# IR-Controle-PC_EasyEDA.net
KiCad netlist of a schematic drawn in EasyEDA
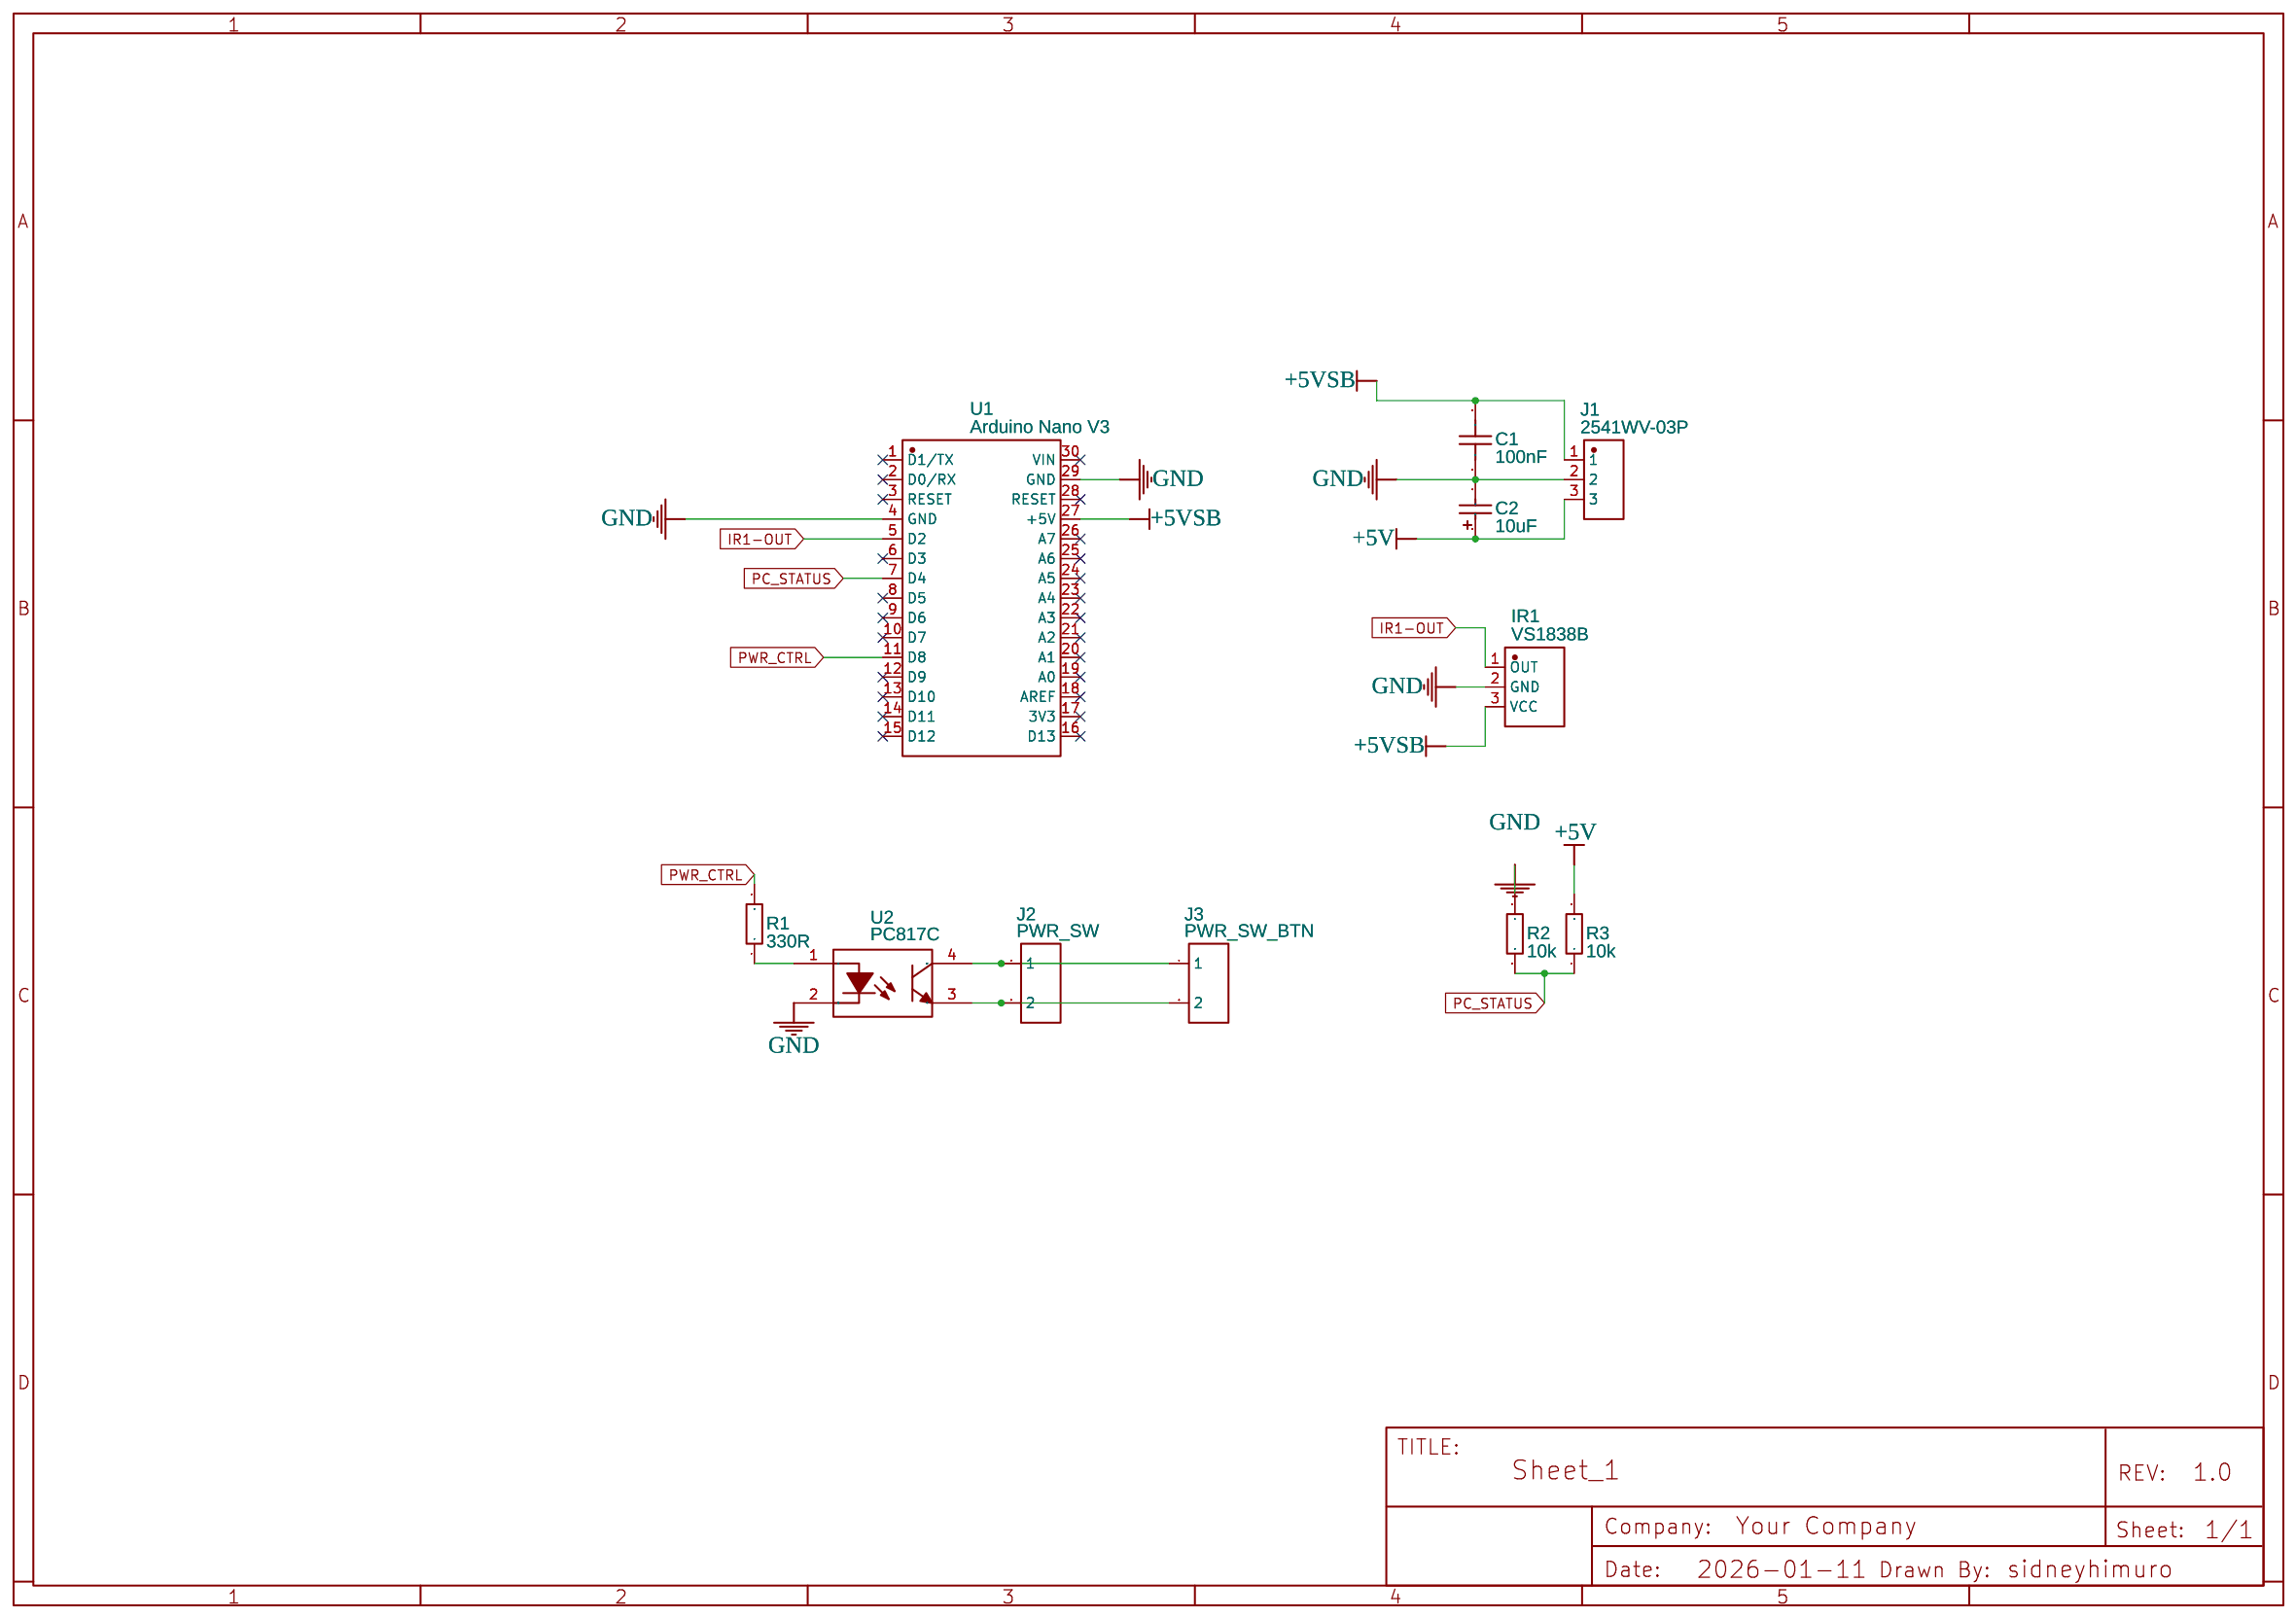
[diagram p0: schematic sheet]

(export (version "E")
  (design (tool "Eeschema 10.0.6"))
  (components
    (comp (ref "C1")
      (value "100nF")
      (fields (field (name "Manufacturer Part") "CT4-0805B103K500F3") (field (name "Manufacturer") "FH"))
      (libsource (lib "") (part "CT4-0805B103K500F3"))
    )
    (comp (ref "C2")
      (value "10uF")
      (fields (field (name "Manufacturer Part") "TAP106K035SCS") (field (name "Manufacturer") "AVX"))
      (libsource (lib "") (part "TAP106K035SCS"))
    )
    (comp (ref "IR1") (value "VS1838B") (libsource (lib "") (part "VS1838B")))
    (comp (ref "J1")
      (value "2541WV-03P")
      (fields (field (name "Manufacturer") "HanElectricity(瀚源)"))
      (libsource (lib "") (part "2541WV-03P"))
    )
    (comp (ref "J2")
      (value "PWR_SW")
      (fields
        (field (name "Manufacturer Part") "826629-2")
        (field (name "Manufacturer") "TE Connectivity(泰科电子)")
      )
      (libsource (lib "") (part "Header-Male-2.54_1x2"))
    )
    (comp (ref "J3")
      (value "PWR_SW_BTN")
      (fields
        (field (name "Manufacturer Part") "826629-2")
        (field (name "Manufacturer") "TE Connectivity(泰科电子)")
      )
      (libsource (lib "") (part "Header-Male-2.54_1x2"))
    )
    (comp (ref "R1")
      (value "330R")
      (fields (field (name "Manufacturer Part") "?"))
      (libsource (lib "") (part "Res_AXIAL-0.3(1/8W)_EU"))
    )
    (comp (ref "R2")
      (value "10k")
      (fields (field (name "Manufacturer Part") "?"))
      (libsource (lib "") (part "Res_AXIAL-0.3(1/8W)_EU_1"))
    )
    (comp (ref "R3")
      (value "10k")
      (fields (field (name "Manufacturer Part") "?"))
      (libsource (lib "") (part "Res_AXIAL-0.3(1/8W)_EU"))
    )
    (comp (ref "U1")
      (value "Arduino Nano V3")
      (fields (field (name "Manufacturer Part") "ARDUINO_NANO"))
      (libsource (lib "") (part "ARDUINO_NANO"))
    )
    (comp (ref "U2")
      (value "PC817C")
      (fields (field (name "Manufacturer") "华润华晶"))
      (libsource (lib "") (part "PC817C"))
    )
  )
  (nets
    (net (code "1") (name "+5V") (class "Default")
      (node (ref "C2") (pin "1") (pinfunction "1_1") (pintype "input"))
      (node (ref "J1") (pin "3") (pinfunction "3_3") (pintype "unspecified"))
      (node (ref "R3") (pin "2") (pinfunction "2_2") (pintype "unspecified"))
    )
    (net (code "2") (name "+5VSB") (class "Default")
      (node (ref "C1") (pin "2") (pinfunction "2_2") (pintype "unspecified"))
      (node (ref "IR1") (pin "3") (pinfunction "VCC_3") (pintype "unspecified"))
      (node (ref "J1") (pin "1") (pinfunction "1_1") (pintype "unspecified"))
      (node (ref "U1") (pin "27") (pinfunction "+5V_27") (pintype "unspecified"))
    )
    (net (code "3") (name "GND") (class "Default")
      (node (ref "C1") (pin "1") (pinfunction "1_1") (pintype "unspecified"))
      (node (ref "C2") (pin "2") (pinfunction "2_2") (pintype "input"))
      (node (ref "IR1") (pin "2") (pinfunction "GND_2") (pintype "unspecified"))
      (node (ref "J1") (pin "2") (pinfunction "2_2") (pintype "unspecified"))
      (node (ref "R2") (pin "1") (pinfunction "1_1") (pintype "unspecified"))
      (node (ref "U1") (pin "29") (pinfunction "GND_29") (pintype "unspecified"))
      (node (ref "U1") (pin "4") (pinfunction "GND_4") (pintype "unspecified"))
      (node (ref "U2") (pin "2") (pinfunction "CAT_2") (pintype "unspecified"))
    )
    (net (code "4") (name "IR1-OUT") (class "Default")
      (node (ref "IR1") (pin "1") (pinfunction "OUT_1") (pintype "unspecified"))
      (node (ref "U1") (pin "5") (pinfunction "D2_5") (pintype "unspecified"))
    )
    (net (code "5") (name "Net-(U2-AN)") (class "Default")
      (node (ref "R1") (pin "1") (pinfunction "1_1") (pintype "unspecified"))
      (node (ref "U2") (pin "1") (pinfunction "AN_1") (pintype "unspecified"))
    )
    (net (code "6") (name "Net-(U2-COL)") (class "Default")
      (node (ref "J2") (pin "1") (pinfunction "1_1") (pintype "unspecified"))
      (node (ref "J3") (pin "1") (pinfunction "1_1") (pintype "unspecified"))
      (node (ref "U2") (pin "4") (pinfunction "COL_4") (pintype "unspecified"))
    )
    (net (code "7") (name "Net-(U2-EM)") (class "Default")
      (node (ref "J2") (pin "2") (pinfunction "2_2") (pintype "unspecified"))
      (node (ref "J3") (pin "2") (pinfunction "2_2") (pintype "unspecified"))
      (node (ref "U2") (pin "3") (pinfunction "EM_3") (pintype "unspecified"))
    )
    (net (code "8") (name "PC_STATUS") (class "Default")
      (node (ref "R2") (pin "2") (pinfunction "2_2") (pintype "unspecified"))
      (node (ref "R3") (pin "1") (pinfunction "1_1") (pintype "unspecified"))
      (node (ref "U1") (pin "7") (pinfunction "D4_7") (pintype "unspecified"))
    )
    (net (code "9") (name "PWR_CTRL") (class "Default")
      (node (ref "R1") (pin "2") (pinfunction "2_2") (pintype "unspecified"))
      (node (ref "U1") (pin "11") (pinfunction "D8_11") (pintype "unspecified"))
    )
    (net (code "10") (name "unconnected-(U1-3V3-Pad17)") (class "Default")
      (node (ref "U1") (pin "17") (pinfunction "3V3_17") (pintype "unspecified+no_connect"))
    )
    (net (code "11") (name "unconnected-(U1-A0-Pad19)") (class "Default")
      (node (ref "U1") (pin "19") (pinfunction "A0_19") (pintype "unspecified+no_connect"))
    )
    (net (code "12") (name "unconnected-(U1-A1-Pad20)") (class "Default")
      (node (ref "U1") (pin "20") (pinfunction "A1_20") (pintype "unspecified+no_connect"))
    )
    (net (code "13") (name "unconnected-(U1-A2-Pad21)") (class "Default")
      (node (ref "U1") (pin "21") (pinfunction "A2_21") (pintype "unspecified+no_connect"))
    )
    (net (code "14") (name "unconnected-(U1-A3-Pad22)") (class "Default")
      (node (ref "U1") (pin "22") (pinfunction "A3_22") (pintype "unspecified+no_connect"))
    )
    (net (code "15") (name "unconnected-(U1-A4-Pad23)") (class "Default")
      (node (ref "U1") (pin "23") (pinfunction "A4_23") (pintype "unspecified+no_connect"))
    )
    (net (code "16") (name "unconnected-(U1-A5-Pad24)") (class "Default")
      (node (ref "U1") (pin "24") (pinfunction "A5_24") (pintype "unspecified+no_connect"))
    )
    (net (code "17") (name "unconnected-(U1-A6-Pad25)") (class "Default")
      (node (ref "U1") (pin "25") (pinfunction "A6_25") (pintype "unspecified+no_connect"))
    )
    (net (code "18") (name "unconnected-(U1-A7-Pad26)") (class "Default")
      (node (ref "U1") (pin "26") (pinfunction "A7_26") (pintype "unspecified+no_connect"))
    )
    (net (code "19") (name "unconnected-(U1-AREF-Pad18)") (class "Default")
      (node (ref "U1") (pin "18") (pinfunction "AREF_18") (pintype "unspecified+no_connect"))
    )
    (net (code "20") (name "unconnected-(U1-D0{slash}RX-Pad2)") (class "Default")
      (node (ref "U1") (pin "2") (pinfunction "D0/RX_2") (pintype "unspecified+no_connect"))
    )
    (net (code "21") (name "unconnected-(U1-D1{slash}TX-Pad1)") (class "Default")
      (node (ref "U1") (pin "1") (pinfunction "D1/TX_1") (pintype "unspecified+no_connect"))
    )
    (net (code "22") (name "unconnected-(U1-D3-Pad6)") (class "Default")
      (node (ref "U1") (pin "6") (pinfunction "D3_6") (pintype "unspecified+no_connect"))
    )
    (net (code "23") (name "unconnected-(U1-D5-Pad8)") (class "Default")
      (node (ref "U1") (pin "8") (pinfunction "D5_8") (pintype "unspecified+no_connect"))
    )
    (net (code "24") (name "unconnected-(U1-D6-Pad9)") (class "Default")
      (node (ref "U1") (pin "9") (pinfunction "D6_9") (pintype "unspecified+no_connect"))
    )
    (net (code "25") (name "unconnected-(U1-D7-Pad10)") (class "Default")
      (node (ref "U1") (pin "10") (pinfunction "D7_10") (pintype "unspecified+no_connect"))
    )
    (net (code "26") (name "unconnected-(U1-D9-Pad12)") (class "Default")
      (node (ref "U1") (pin "12") (pinfunction "D9_12") (pintype "unspecified+no_connect"))
    )
    (net (code "27") (name "unconnected-(U1-D10-Pad13)") (class "Default")
      (node (ref "U1") (pin "13") (pinfunction "D10_13") (pintype "unspecified+no_connect"))
    )
    (net (code "28") (name "unconnected-(U1-D11-Pad14)") (class "Default")
      (node (ref "U1") (pin "14") (pinfunction "D11_14") (pintype "unspecified+no_connect"))
    )
    (net (code "29") (name "unconnected-(U1-D12-Pad15)") (class "Default")
      (node (ref "U1") (pin "15") (pinfunction "D12_15") (pintype "unspecified+no_connect"))
    )
    (net (code "30") (name "unconnected-(U1-D13-Pad16)") (class "Default")
      (node (ref "U1") (pin "16") (pinfunction "D13_16") (pintype "unspecified+no_connect"))
    )
    (net (code "31") (name "unconnected-(U1-RESET-Pad3)") (class "Default")
      (node (ref "U1") (pin "3") (pinfunction "RESET_3") (pintype "unspecified+no_connect"))
    )
    (net (code "32") (name "unconnected-(U1-RESET-Pad28)") (class "Default")
      (node (ref "U1") (pin "28") (pinfunction "RESET_28") (pintype "unspecified+no_connect"))
    )
    (net (code "33") (name "unconnected-(U1-VIN-Pad30)") (class "Default")
      (node (ref "U1") (pin "30") (pinfunction "VIN_30") (pintype "unspecified+no_connect"))
    )
  )
)
